# RS-485.net
KiCad netlist of a schematic drawn in Altium Designer
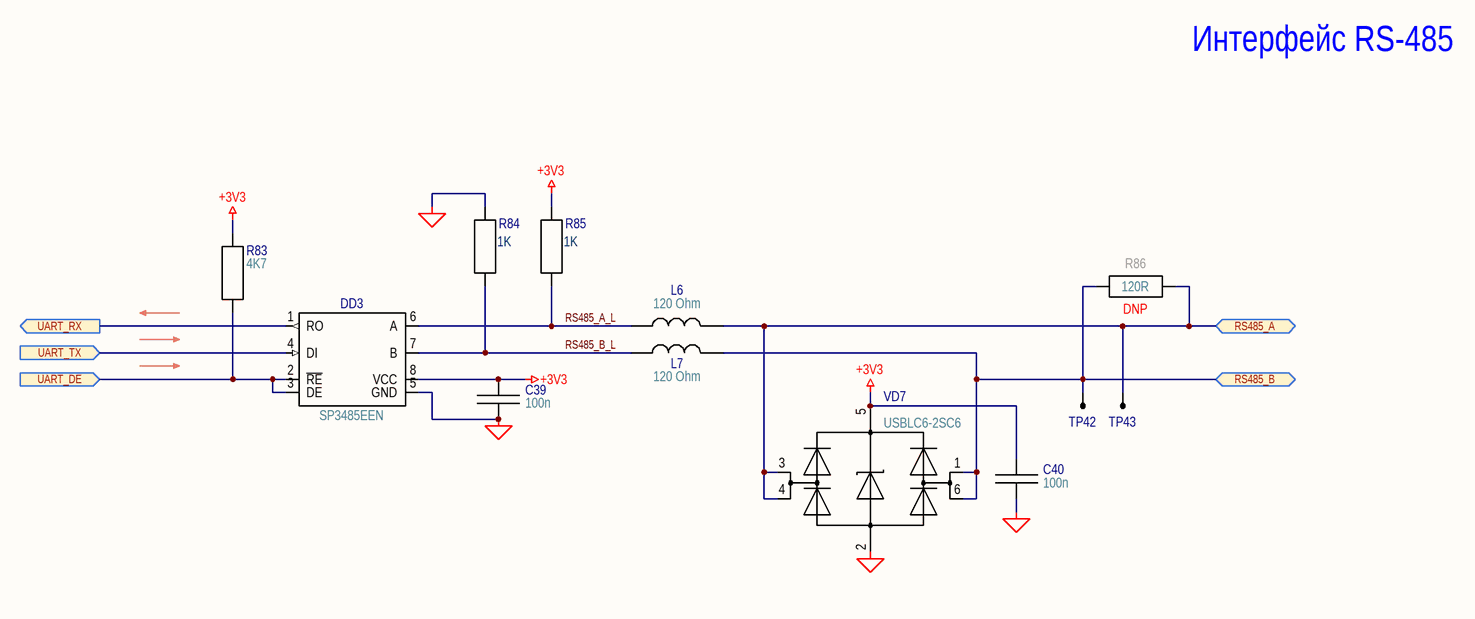
[diagram p0: RS-485.SchDoc]

(export (version "E")
  (design (tool "Eeschema 10.0.6"))
  (components
    (comp (ref "C39")
      (value "100n")
      (footprint "C0402")
      (description "Чип-конденсатор 100 нФ 10% 50 В X7R 0402")
      (fields
        (field (name "MANUFACTURER PART NUMBER") "CC0402KRX7R9BB104")
        (field (name "MANUFACTURER") "Yageo")
      )
      (libsource (lib "ums") (part "C0402"))
    )
    (comp (ref "C40")
      (value "100n")
      (footprint "C0402")
      (description "Чип-конденсатор 100 нФ 10% 50 В X7R 0402")
      (fields
        (field (name "MANUFACTURER PART NUMBER") "CC0402KRX7R9BB104")
        (field (name "MANUFACTURER") "Yageo")
      )
      (libsource (lib "ums") (part "C0402"))
    )
    (comp (ref "DD3")
      (value "SP3485EEN")
      (footprint "SOP-8")
      (description "Трансивер RS-485 SP3485EEN")
      (fields (field (name "MANUFACTURER") "UMW"))
      (libsource (lib "ums") (part "SP3485EEN"))
    )
    (comp (ref "L6")
      (value "120 Ohm")
      (footprint "BLM18PG")
      (description "Фильтр индуктивный 120 Ом @ 100 МГц 2 А 0603")
      (fields
        (field (name "MANUFACTURER") "FENGHUA Advanced Technology")
        (field (name "MANUFACTURER PART NUMBER") "CBM160808U121T")
      )
      (libsource (lib "ums") (part "BLM18PG121SN1D"))
    )
    (comp (ref "L7")
      (value "120 Ohm")
      (footprint "BLM18PG")
      (description "Фильтр индуктивный 120 Ом @ 100 МГц 2 А 0603")
      (fields
        (field (name "MANUFACTURER") "FENGHUA Advanced Technology")
        (field (name "MANUFACTURER PART NUMBER") "CBM160808U121T")
      )
      (libsource (lib "ums") (part "BLM18PG121SN1D"))
    )
    (comp (ref "R83")
      (value "4K7")
      (footprint "R0402")
      (description "Чип-резистор 4,7 кОм 1% 0402")
      (fields
        (field (name "MANUFACTURER PART NUMBER") "RC0402FR-074K7L")
        (field (name "MANUFACTURER") "Yageo")
      )
      (libsource (lib "ums") (part "R0402"))
    )
    (comp (ref "R84")
      (value "1K")
      (footprint "R0402")
      (description "Чип-резистор 1 кОм 1% 0402")
      (fields
        (field (name "MANUFACTURER PART NUMBER") "RC0402FR-071KL")
        (field (name "MANUFACTURER") "Yageo")
      )
      (libsource (lib "ums") (part "R0402_4"))
    )
    (comp (ref "R85")
      (value "1K")
      (footprint "R0402")
      (description "Чип-резистор 1 кОм 1% 0402")
      (fields
        (field (name "MANUFACTURER PART NUMBER") "RC0402FR-071KL")
        (field (name "MANUFACTURER") "Yageo")
      )
      (libsource (lib "ums") (part "R0402_4"))
    )
    (comp (ref "R86")
      (value "120R")
      (footprint "R0805_ROUNDED")
      (description "Чип-резистор 120 Ом 1% 0805")
      (fields
        (field (name "MANUFACTURER PART NUMBER") "RC0805FR-07120RL")
        (field (name "MANUFACTURER") "Yageo")
      )
      (libsource (lib "ums") (part "R0805"))
    )
    (comp (ref "TP42")
      (value "TEST_POINT_1.27_STEP")
      (footprint "TEST_POINT_1.27_STEP")
      (description "Контрольная точка SMD")
      (libsource (lib "ums") (part "TEST_POINT_1.27_STEP"))
    )
    (comp (ref "TP43")
      (value "TEST_POINT_1.27_STEP")
      (footprint "TEST_POINT_1.27_STEP")
      (description "Контрольная точка SMD")
      (libsource (lib "ums") (part "TEST_POINT_1.27_STEP"))
    )
    (comp (ref "VD7")
      (value "USBLC6-2SC6")
      (footprint "SOT-23-6-USBLC-Internal-Jumpers")
      (description "Диодная сборка ESD защиты USBLC6-2SC6")
      (fields (field (name "MANUFACTURER") "UMW"))
      (libsource (lib "ums") (part "USBLC6-2SC6"))
    )
  )
  (nets
    (net (code "1") (name "+3V3") (class "Default")
      (node (ref "C39") (pin "2") (pinfunction "2_2") (pintype "passive"))
      (node (ref "C40") (pin "2") (pinfunction "2_2") (pintype "passive"))
      (node (ref "DD3") (pin "8") (pinfunction "VCC_8") (pintype "passive"))
      (node (ref "R83") (pin "2") (pinfunction "2_2") (pintype "passive"))
      (node (ref "R85") (pin "2") (pinfunction "2_2") (pintype "passive"))
      (node (ref "VD7") (pin "5") (pinfunction "5_5") (pintype "passive"))
    )
    (net (code "3") (name "/RS485_A") (class "Default")
      (node (ref "L6") (pin "2") (pinfunction "2_2") (pintype "passive"))
      (node (ref "R86") (pin "2") (pinfunction "2_2") (pintype "passive"))
      (node (ref "TP43") (pin "1") (pinfunction "1_1") (pintype "passive"))
      (node (ref "VD7") (pin "3") (pinfunction "3_3") (pintype "passive"))
      (node (ref "VD7") (pin "4") (pinfunction "4_4") (pintype "passive"))
    )
    (net (code "4") (name "/RS485_A_L") (class "Default")
      (node (ref "DD3") (pin "6") (pinfunction "A_6") (pintype "passive"))
      (node (ref "L6") (pin "1") (pinfunction "1_1") (pintype "passive"))
      (node (ref "R85") (pin "1") (pinfunction "1_1") (pintype "passive"))
    )
    (net (code "5") (name "/RS485_B") (class "Default")
      (node (ref "L7") (pin "2") (pinfunction "2_2") (pintype "passive"))
      (node (ref "R86") (pin "1") (pinfunction "1_1") (pintype "passive"))
      (node (ref "TP42") (pin "1") (pinfunction "1_1") (pintype "passive"))
      (node (ref "VD7") (pin "1") (pinfunction "1_1") (pintype "passive"))
      (node (ref "VD7") (pin "6") (pinfunction "6_6") (pintype "passive"))
    )
    (net (code "6") (name "/RS485_B_L") (class "Default")
      (node (ref "DD3") (pin "7") (pinfunction "B_7") (pintype "passive"))
      (node (ref "L7") (pin "1") (pinfunction "1_1") (pintype "passive"))
      (node (ref "R84") (pin "1") (pinfunction "1_1") (pintype "passive"))
    )
    (net (code "7") (name "/UART_DE") (class "Default")
      (node (ref "DD3") (pin "2") (pinfunction "~{RE}_2") (pintype "passive"))
      (node (ref "DD3") (pin "3") (pinfunction "DE_3") (pintype "passive"))
      (node (ref "R83") (pin "1") (pinfunction "1_1") (pintype "passive"))
    )
    (net (code "8") (name "/UART_RX") (class "Default")
      (node (ref "DD3") (pin "1") (pinfunction "RO_1") (pintype "output"))
    )
    (net (code "9") (name "/UART_TX") (class "Default")
      (node (ref "DD3") (pin "4") (pinfunction "DI_4") (pintype "input"))
    )
    (net (code "10") (name "GND") (class "Default")
      (node (ref "C39") (pin "1") (pinfunction "1_1") (pintype "passive"))
      (node (ref "C40") (pin "1") (pinfunction "1_1") (pintype "passive"))
      (node (ref "DD3") (pin "5") (pinfunction "GND_5") (pintype "passive"))
      (node (ref "R84") (pin "2") (pinfunction "2_2") (pintype "passive"))
      (node (ref "VD7") (pin "2") (pinfunction "2_2") (pintype "passive"))
    )
  )
)
